# LedRGB.net
KiCad netlist of a schematic drawn in Altium Designer
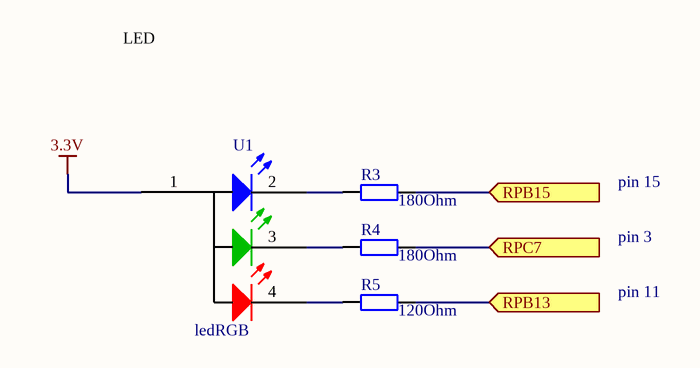
[diagram p0: LedRGB.SchDoc]

(export (version "E")
  (design (tool "Eeschema 10.0.6"))
  (components
    (comp (ref "R3")
      (value "180Ohm")
      (footprint "0603")
      (description "Resistor")
      (fields (field (name "Comment") "Res2") (field (name "PUBLISHER") "Altium Limited"))
      (libsource (lib "Miscellaneous Devices") (part "Res2"))
    )
    (comp (ref "R4")
      (value "180Ohm")
      (footprint "0603")
      (description "Resistor")
      (fields (field (name "Comment") "Res2") (field (name "PUBLISHER") "Altium Limited"))
      (libsource (lib "Miscellaneous Devices") (part "Res2"))
    )
    (comp (ref "R5")
      (value "120Ohm")
      (footprint "0603")
      (description "Resistor")
      (fields (field (name "Comment") "Res2") (field (name "PUBLISHER") "Altium Limited"))
      (libsource (lib "Miscellaneous Devices") (part "Res2"))
    )
    (comp (ref "U1") (value "ledRGB") (footprint "LED RGB") (libsource (lib "Schlib1") (part "ledRGB")))
  )
  (nets
    (net (code "1") (name "/RPB13") (class "Default")
      (node (ref "R5") (pin "2") (pinfunction "2_2") (pintype "passive"))
    )
    (net (code "2") (name "/RPB15") (class "Default")
      (node (ref "R3") (pin "2") (pinfunction "2_2") (pintype "passive"))
    )
    (net (code "3") (name "/RPC7") (class "Default")
      (node (ref "R4") (pin "2") (pinfunction "2_2") (pintype "passive"))
    )
    (net (code "4") (name "3.3V") (class "Default")
      (node (ref "U1") (pin "1") (pinfunction "1_1") (pintype "passive"))
    )
    (net (code "5") (name "Net-(R3-Pad1)") (class "Default")
      (node (ref "R3") (pin "1") (pinfunction "1_1") (pintype "passive"))
      (node (ref "U1") (pin "2") (pinfunction "2_2") (pintype "passive"))
    )
    (net (code "6") (name "Net-(R4-Pad1)") (class "Default")
      (node (ref "R4") (pin "1") (pinfunction "1_1") (pintype "passive"))
      (node (ref "U1") (pin "3") (pinfunction "3_3") (pintype "passive"))
    )
    (net (code "7") (name "Net-(R5-Pad1)") (class "Default")
      (node (ref "R5") (pin "1") (pinfunction "1_1") (pintype "passive"))
      (node (ref "U1") (pin "4") (pinfunction "4_4") (pintype "passive"))
    )
  )
)
